# arabaKonsolSematik.net
KiCad netlist of a schematic drawn in Altium Designer
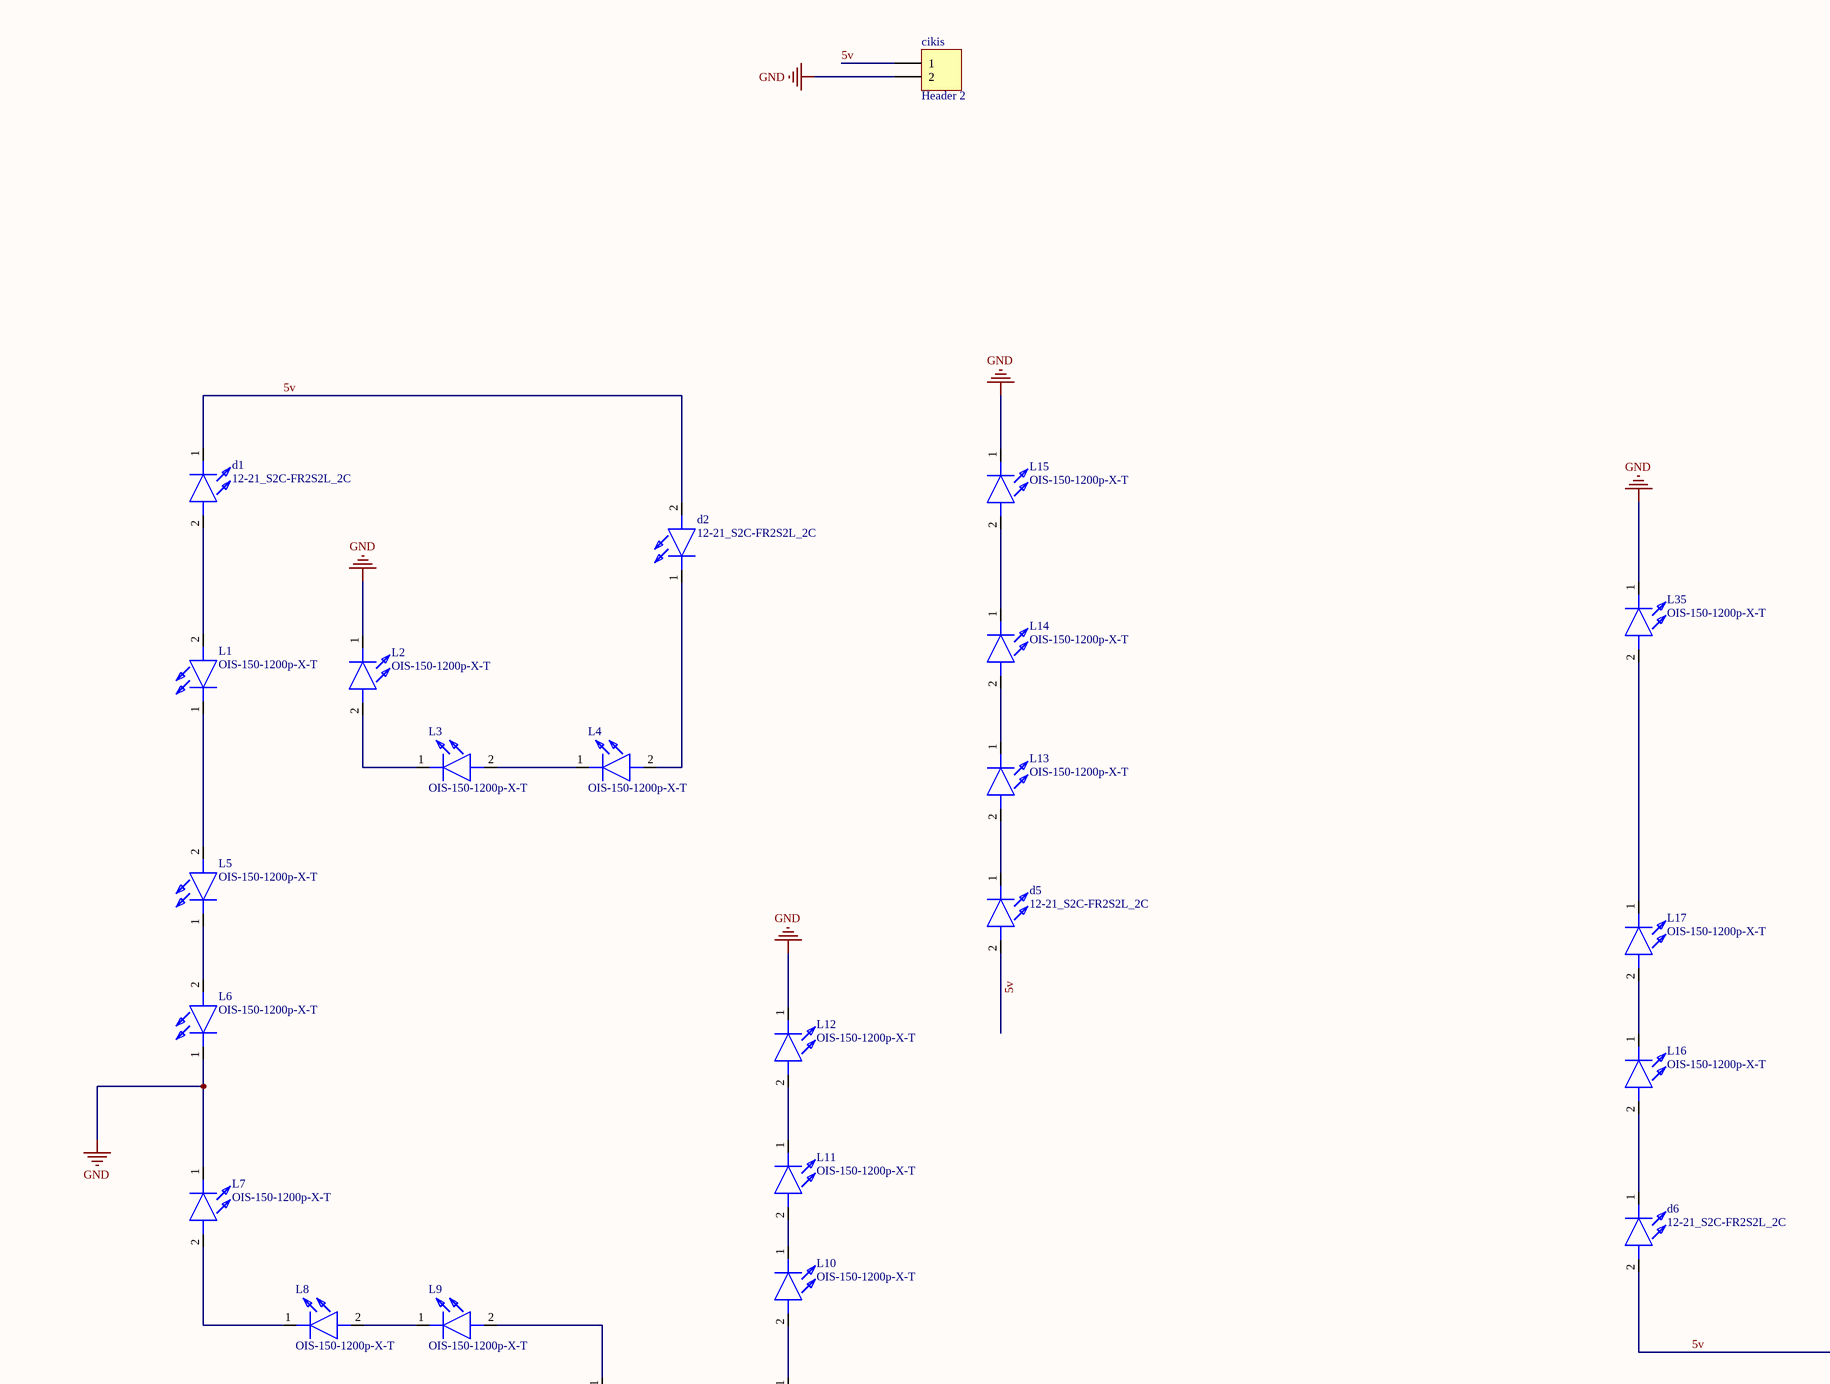
[diagram p0: arabaKonsolSematik.SchDoc, top left]
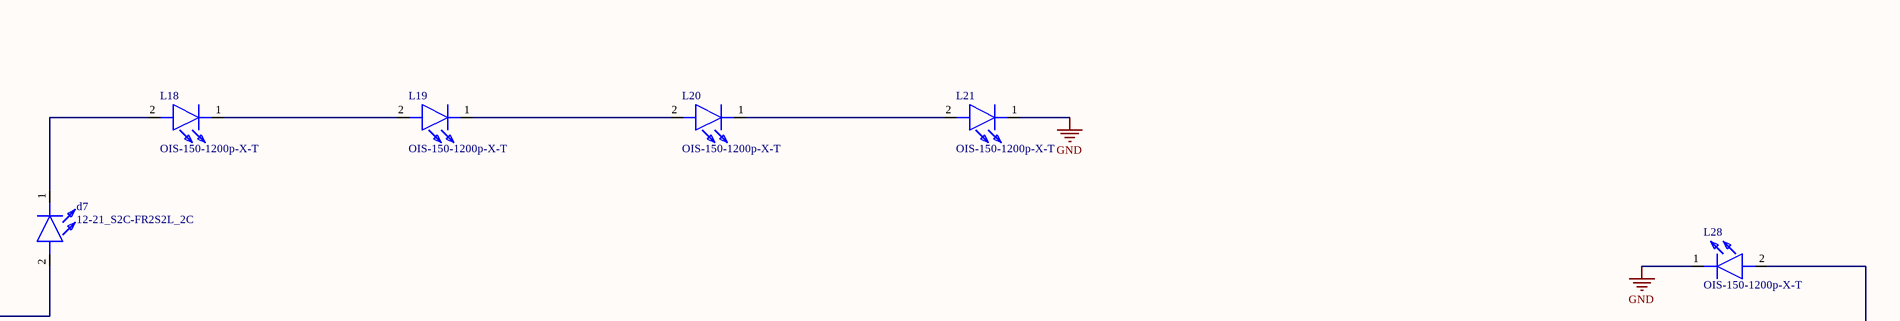
[diagram p1: arabaKonsolSematik.SchDoc, top right]
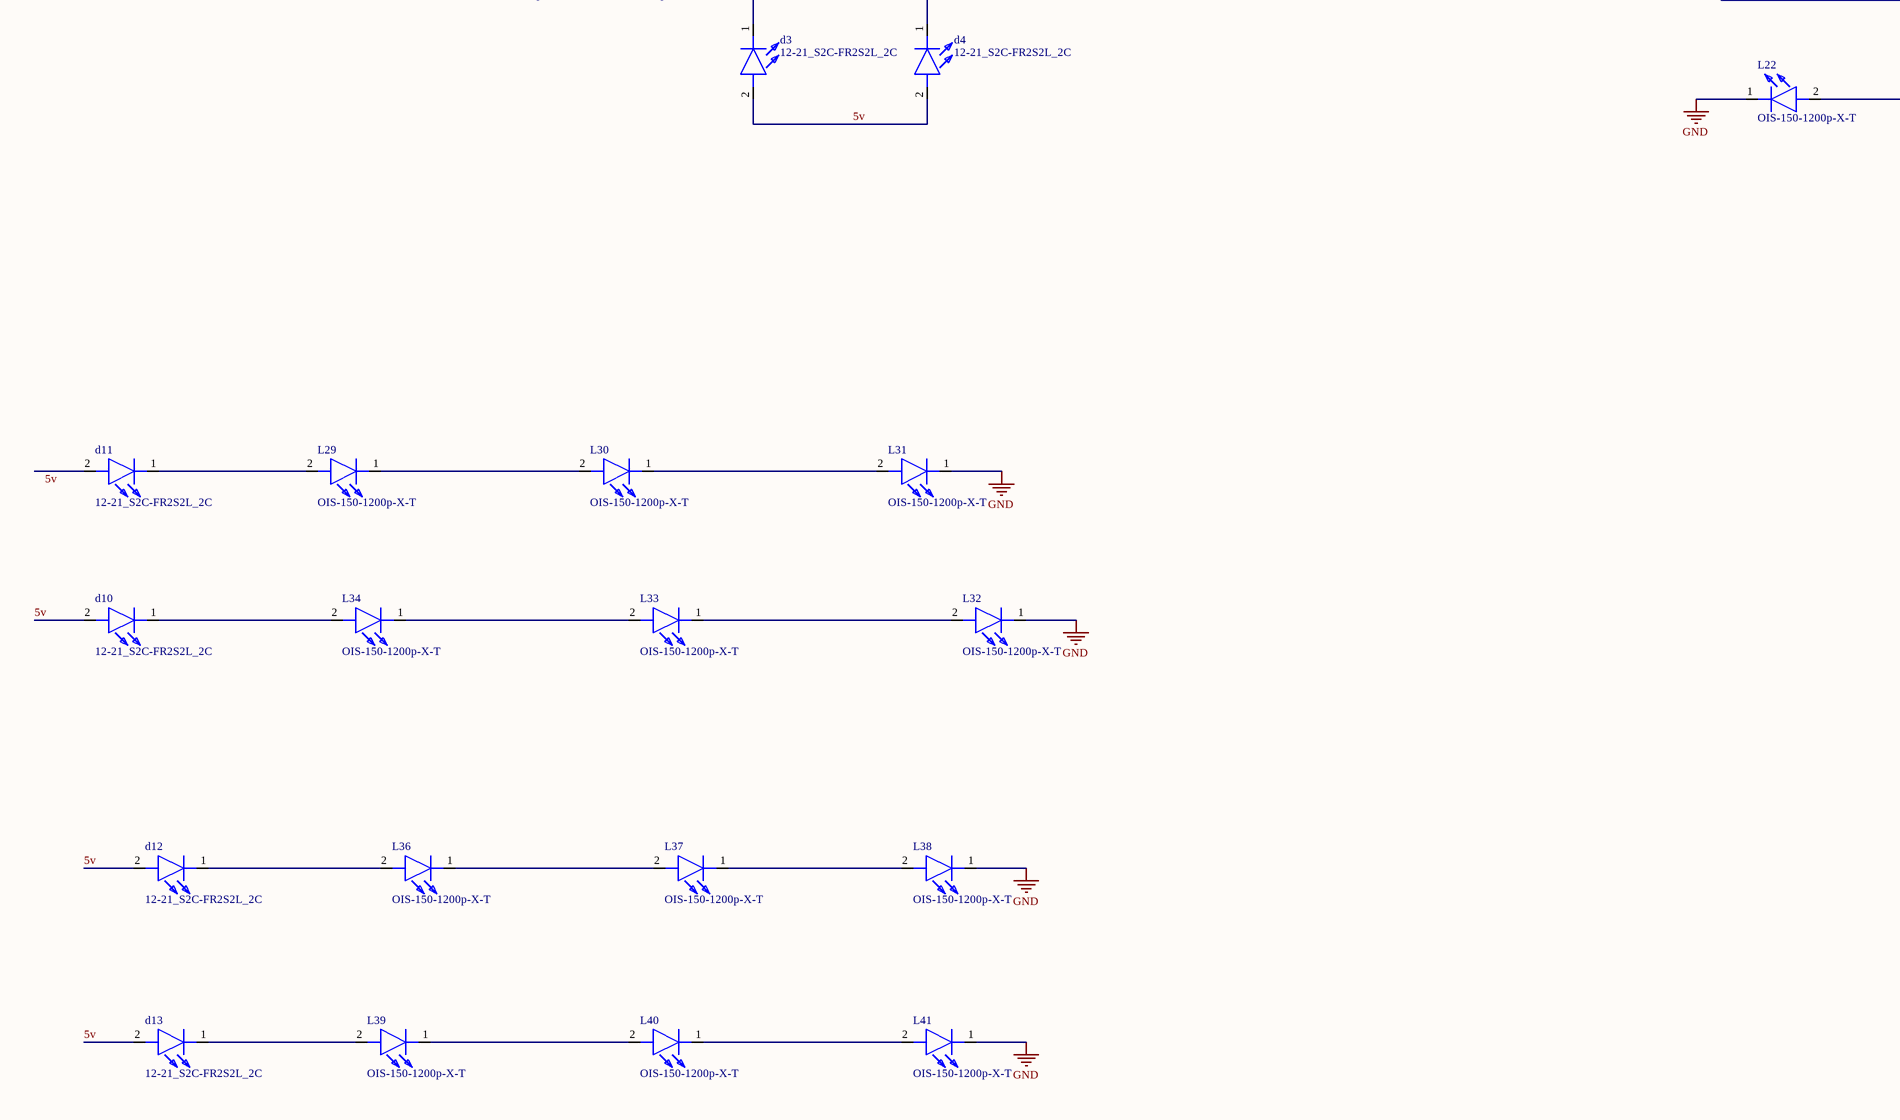
[diagram p2: arabaKonsolSematik.SchDoc, bottom left]
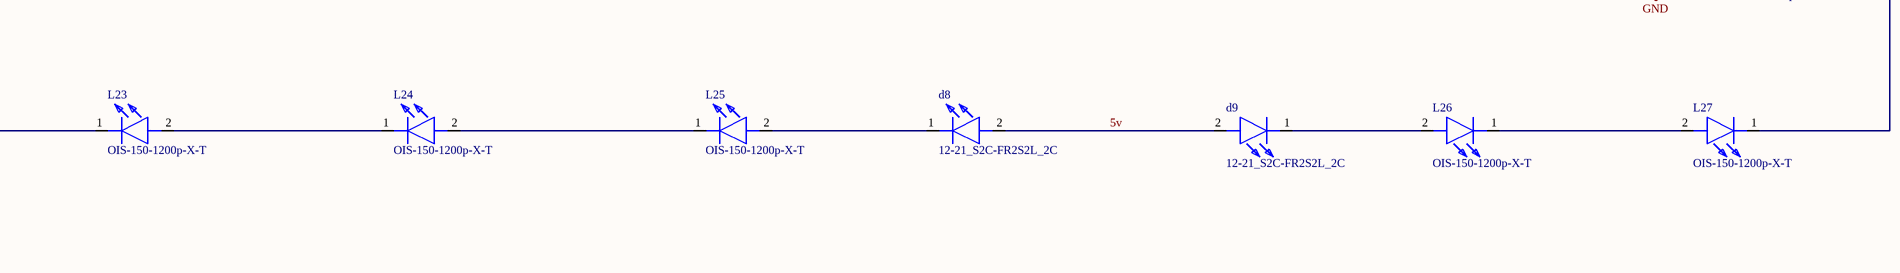
[diagram p3: arabaKonsolSematik.SchDoc, bottom right]

(export (version "E")
  (design (tool "Eeschema 10.0.6"))
  (components
    (comp (ref "cikis")
      (value "Header 2")
      (footprint "HDR1X2")
      (description "Header, 2-Pin")
      (fields (field (name "PUBLISHER") "Altium Limited"))
      (libsource (lib "Miscellaneous Connectors") (part "Header 2"))
    )
    (comp (ref "d1")
      (value "12-21_S2C-FR2S2L_2C")
      (footprint "SamacSys:1221S2CFR2S2L2C")
      (description "LED")
      (fields (field (name "MANUFACTURER_PART_NUMBER") "12-21/S2C-FR2S2L/2C"))
      (libsource (lib "SamacSys") (part "12-21_S2C-FR2S2L_2C"))
    )
    (comp (ref "d2")
      (value "12-21_S2C-FR2S2L_2C")
      (footprint "SamacSys:1221S2CFR2S2L2C")
      (description "LED")
      (fields (field (name "MANUFACTURER_PART_NUMBER") "12-21/S2C-FR2S2L/2C"))
      (libsource (lib "SamacSys") (part "12-21_S2C-FR2S2L_2C"))
    )
    (comp (ref "d3")
      (value "12-21_S2C-FR2S2L_2C")
      (footprint "SamacSys:1221S2CFR2S2L2C")
      (description "LED")
      (fields (field (name "MANUFACTURER_PART_NUMBER") "12-21/S2C-FR2S2L/2C"))
      (libsource (lib "SamacSys") (part "12-21_S2C-FR2S2L_2C"))
    )
    (comp (ref "d4")
      (value "12-21_S2C-FR2S2L_2C")
      (footprint "SamacSys:1221S2CFR2S2L2C")
      (description "LED")
      (fields (field (name "MANUFACTURER_PART_NUMBER") "12-21/S2C-FR2S2L/2C"))
      (libsource (lib "SamacSys") (part "12-21_S2C-FR2S2L_2C"))
    )
    (comp (ref "d5")
      (value "12-21_S2C-FR2S2L_2C")
      (footprint "SamacSys:1221S2CFR2S2L2C")
      (description "LED")
      (fields (field (name "MANUFACTURER_PART_NUMBER") "12-21/S2C-FR2S2L/2C"))
      (libsource (lib "SamacSys") (part "12-21_S2C-FR2S2L_2C"))
    )
    (comp (ref "d6")
      (value "12-21_S2C-FR2S2L_2C")
      (footprint "SamacSys:1221S2CFR2S2L2C")
      (description "LED")
      (fields (field (name "MANUFACTURER_PART_NUMBER") "12-21/S2C-FR2S2L/2C"))
      (libsource (lib "SamacSys") (part "12-21_S2C-FR2S2L_2C"))
    )
    (comp (ref "d7")
      (value "12-21_S2C-FR2S2L_2C")
      (footprint "SamacSys:1221S2CFR2S2L2C")
      (description "LED")
      (fields (field (name "MANUFACTURER_PART_NUMBER") "12-21/S2C-FR2S2L/2C"))
      (libsource (lib "SamacSys") (part "12-21_S2C-FR2S2L_2C"))
    )
    (comp (ref "d8")
      (value "12-21_S2C-FR2S2L_2C")
      (footprint "SamacSys:1221S2CFR2S2L2C")
      (description "LED")
      (fields (field (name "MANUFACTURER_PART_NUMBER") "12-21/S2C-FR2S2L/2C"))
      (libsource (lib "SamacSys") (part "12-21_S2C-FR2S2L_2C"))
    )
    (comp (ref "d9")
      (value "12-21_S2C-FR2S2L_2C")
      (footprint "SamacSys:1221S2CFR2S2L2C")
      (description "LED")
      (fields (field (name "MANUFACTURER_PART_NUMBER") "12-21/S2C-FR2S2L/2C"))
      (libsource (lib "SamacSys") (part "12-21_S2C-FR2S2L_2C"))
    )
    (comp (ref "d10")
      (value "12-21_S2C-FR2S2L_2C")
      (footprint "SamacSys:1221S2CFR2S2L2C")
      (description "LED")
      (fields (field (name "MANUFACTURER_PART_NUMBER") "12-21/S2C-FR2S2L/2C"))
      (libsource (lib "SamacSys") (part "12-21_S2C-FR2S2L_2C"))
    )
    (comp (ref "d11")
      (value "12-21_S2C-FR2S2L_2C")
      (footprint "SamacSys:1221S2CFR2S2L2C")
      (description "LED")
      (fields (field (name "MANUFACTURER_PART_NUMBER") "12-21/S2C-FR2S2L/2C"))
      (libsource (lib "SamacSys") (part "12-21_S2C-FR2S2L_2C"))
    )
    (comp (ref "d12")
      (value "12-21_S2C-FR2S2L_2C")
      (footprint "SamacSys:1221S2CFR2S2L2C")
      (description "LED")
      (fields (field (name "MANUFACTURER_PART_NUMBER") "12-21/S2C-FR2S2L/2C"))
      (libsource (lib "SamacSys") (part "12-21_S2C-FR2S2L_2C"))
    )
    (comp (ref "d13")
      (value "12-21_S2C-FR2S2L_2C")
      (footprint "SamacSys:1221S2CFR2S2L2C")
      (description "LED")
      (fields (field (name "MANUFACTURER_PART_NUMBER") "12-21/S2C-FR2S2L/2C"))
      (libsource (lib "SamacSys") (part "12-21_S2C-FR2S2L_2C"))
    )
    (comp (ref "L1")
      (value "OIS-150-1200p-X-T")
      (footprint "SamacSys:LEDC3216X120N")
      (description "LED")
      (libsource (lib "*") (part "OIS-150-1200p-X-T"))
    )
    (comp (ref "L2")
      (value "OIS-150-1200p-X-T")
      (footprint "SamacSys:LEDC3216X120N")
      (description "LED")
      (libsource (lib "*") (part "OIS-150-1200p-X-T"))
    )
    (comp (ref "L3")
      (value "OIS-150-1200p-X-T")
      (footprint "SamacSys:LEDC3216X120N")
      (description "LED")
      (libsource (lib "*") (part "OIS-150-1200p-X-T"))
    )
    (comp (ref "L4")
      (value "OIS-150-1200p-X-T")
      (footprint "SamacSys:LEDC3216X120N")
      (description "LED")
      (libsource (lib "*") (part "OIS-150-1200p-X-T"))
    )
    (comp (ref "L5")
      (value "OIS-150-1200p-X-T")
      (footprint "SamacSys:LEDC3216X120N")
      (description "LED")
      (libsource (lib "*") (part "OIS-150-1200p-X-T"))
    )
    (comp (ref "L6")
      (value "OIS-150-1200p-X-T")
      (footprint "SamacSys:LEDC3216X120N")
      (description "LED")
      (libsource (lib "*") (part "OIS-150-1200p-X-T"))
    )
    (comp (ref "L7")
      (value "OIS-150-1200p-X-T")
      (footprint "SamacSys:LEDC3216X120N")
      (description "LED")
      (libsource (lib "*") (part "OIS-150-1200p-X-T"))
    )
    (comp (ref "L8")
      (value "OIS-150-1200p-X-T")
      (footprint "SamacSys:LEDC3216X120N")
      (description "LED")
      (libsource (lib "*") (part "OIS-150-1200p-X-T"))
    )
    (comp (ref "L9")
      (value "OIS-150-1200p-X-T")
      (footprint "SamacSys:LEDC3216X120N")
      (description "LED")
      (libsource (lib "*") (part "OIS-150-1200p-X-T"))
    )
    (comp (ref "L10")
      (value "OIS-150-1200p-X-T")
      (footprint "SamacSys:LEDC3216X120N")
      (description "LED")
      (libsource (lib "*") (part "OIS-150-1200p-X-T"))
    )
    (comp (ref "L11")
      (value "OIS-150-1200p-X-T")
      (footprint "SamacSys:LEDC3216X120N")
      (description "LED")
      (libsource (lib "*") (part "OIS-150-1200p-X-T"))
    )
    (comp (ref "L12")
      (value "OIS-150-1200p-X-T")
      (footprint "SamacSys:LEDC3216X120N")
      (description "LED")
      (libsource (lib "*") (part "OIS-150-1200p-X-T"))
    )
    (comp (ref "L13")
      (value "OIS-150-1200p-X-T")
      (footprint "SamacSys:LEDC3216X120N")
      (description "LED")
      (libsource (lib "*") (part "OIS-150-1200p-X-T"))
    )
    (comp (ref "L14")
      (value "OIS-150-1200p-X-T")
      (footprint "SamacSys:LEDC3216X120N")
      (description "LED")
      (libsource (lib "*") (part "OIS-150-1200p-X-T"))
    )
    (comp (ref "L15")
      (value "OIS-150-1200p-X-T")
      (footprint "SamacSys:LEDC3216X120N")
      (description "LED")
      (libsource (lib "*") (part "OIS-150-1200p-X-T"))
    )
    (comp (ref "L16")
      (value "OIS-150-1200p-X-T")
      (footprint "SamacSys:LEDC3216X120N")
      (description "LED")
      (libsource (lib "*") (part "OIS-150-1200p-X-T"))
    )
    (comp (ref "L17")
      (value "OIS-150-1200p-X-T")
      (footprint "SamacSys:LEDC3216X120N")
      (description "LED")
      (libsource (lib "*") (part "OIS-150-1200p-X-T"))
    )
    (comp (ref "L18")
      (value "OIS-150-1200p-X-T")
      (footprint "SamacSys:LEDC3216X120N")
      (description "LED")
      (libsource (lib "*") (part "OIS-150-1200p-X-T"))
    )
    (comp (ref "L19")
      (value "OIS-150-1200p-X-T")
      (footprint "SamacSys:LEDC3216X120N")
      (description "LED")
      (libsource (lib "*") (part "OIS-150-1200p-X-T"))
    )
    (comp (ref "L20")
      (value "OIS-150-1200p-X-T")
      (footprint "SamacSys:LEDC3216X120N")
      (description "LED")
      (libsource (lib "*") (part "OIS-150-1200p-X-T"))
    )
    (comp (ref "L21")
      (value "OIS-150-1200p-X-T")
      (footprint "SamacSys:LEDC3216X120N")
      (description "LED")
      (libsource (lib "*") (part "OIS-150-1200p-X-T"))
    )
    (comp (ref "L22")
      (value "OIS-150-1200p-X-T")
      (footprint "SamacSys:LEDC3216X120N")
      (description "LED")
      (libsource (lib "*") (part "OIS-150-1200p-X-T"))
    )
    (comp (ref "L23")
      (value "OIS-150-1200p-X-T")
      (footprint "SamacSys:LEDC3216X120N")
      (description "LED")
      (libsource (lib "*") (part "OIS-150-1200p-X-T"))
    )
    (comp (ref "L24")
      (value "OIS-150-1200p-X-T")
      (footprint "SamacSys:LEDC3216X120N")
      (description "LED")
      (libsource (lib "*") (part "OIS-150-1200p-X-T"))
    )
    (comp (ref "L25")
      (value "OIS-150-1200p-X-T")
      (footprint "SamacSys:LEDC3216X120N")
      (description "LED")
      (libsource (lib "*") (part "OIS-150-1200p-X-T"))
    )
    (comp (ref "L26")
      (value "OIS-150-1200p-X-T")
      (footprint "SamacSys:LEDC3216X120N")
      (description "LED")
      (libsource (lib "*") (part "OIS-150-1200p-X-T"))
    )
    (comp (ref "L27")
      (value "OIS-150-1200p-X-T")
      (footprint "SamacSys:LEDC3216X120N")
      (description "LED")
      (libsource (lib "*") (part "OIS-150-1200p-X-T"))
    )
    (comp (ref "L28")
      (value "OIS-150-1200p-X-T")
      (footprint "SamacSys:LEDC3216X120N")
      (description "LED")
      (libsource (lib "*") (part "OIS-150-1200p-X-T"))
    )
    (comp (ref "L29")
      (value "OIS-150-1200p-X-T")
      (footprint "SamacSys:LEDC3216X120N")
      (description "LED")
      (libsource (lib "*") (part "OIS-150-1200p-X-T"))
    )
    (comp (ref "L30")
      (value "OIS-150-1200p-X-T")
      (footprint "SamacSys:LEDC3216X120N")
      (description "LED")
      (libsource (lib "*") (part "OIS-150-1200p-X-T"))
    )
    (comp (ref "L31")
      (value "OIS-150-1200p-X-T")
      (footprint "SamacSys:LEDC3216X120N")
      (description "LED")
      (libsource (lib "*") (part "OIS-150-1200p-X-T"))
    )
    (comp (ref "L32")
      (value "OIS-150-1200p-X-T")
      (footprint "SamacSys:LEDC3216X120N")
      (description "LED")
      (libsource (lib "*") (part "OIS-150-1200p-X-T"))
    )
    (comp (ref "L33")
      (value "OIS-150-1200p-X-T")
      (footprint "SamacSys:LEDC3216X120N")
      (description "LED")
      (libsource (lib "*") (part "OIS-150-1200p-X-T"))
    )
    (comp (ref "L34")
      (value "OIS-150-1200p-X-T")
      (footprint "SamacSys:LEDC3216X120N")
      (description "LED")
      (libsource (lib "*") (part "OIS-150-1200p-X-T"))
    )
    (comp (ref "L35")
      (value "OIS-150-1200p-X-T")
      (footprint "SamacSys:LEDC3216X120N")
      (description "LED")
      (libsource (lib "*") (part "OIS-150-1200p-X-T"))
    )
    (comp (ref "L36")
      (value "OIS-150-1200p-X-T")
      (footprint "SamacSys:LEDC3216X120N")
      (description "LED")
      (libsource (lib "*") (part "OIS-150-1200p-X-T"))
    )
    (comp (ref "L37")
      (value "OIS-150-1200p-X-T")
      (footprint "SamacSys:LEDC3216X120N")
      (description "LED")
      (libsource (lib "*") (part "OIS-150-1200p-X-T"))
    )
    (comp (ref "L38")
      (value "OIS-150-1200p-X-T")
      (footprint "SamacSys:LEDC3216X120N")
      (description "LED")
      (libsource (lib "*") (part "OIS-150-1200p-X-T"))
    )
    (comp (ref "L39")
      (value "OIS-150-1200p-X-T")
      (footprint "SamacSys:LEDC3216X120N")
      (description "LED")
      (libsource (lib "*") (part "OIS-150-1200p-X-T"))
    )
    (comp (ref "L40")
      (value "OIS-150-1200p-X-T")
      (footprint "SamacSys:LEDC3216X120N")
      (description "LED")
      (libsource (lib "*") (part "OIS-150-1200p-X-T"))
    )
    (comp (ref "L41")
      (value "OIS-150-1200p-X-T")
      (footprint "SamacSys:LEDC3216X120N")
      (description "LED")
      (libsource (lib "*") (part "OIS-150-1200p-X-T"))
    )
  )
  (nets
    (net (code "1") (name "/5v") (class "Default")
      (node (ref "cikis") (pin "1") (pinfunction "1_1") (pintype "passive"))
      (node (ref "d1") (pin "1") (pinfunction "K_1") (pintype "passive"))
      (node (ref "d10") (pin "2") (pinfunction "A_2") (pintype "passive"))
      (node (ref "d11") (pin "2") (pinfunction "A_2") (pintype "passive"))
      (node (ref "d12") (pin "2") (pinfunction "A_2") (pintype "passive"))
      (node (ref "d13") (pin "2") (pinfunction "A_2") (pintype "passive"))
      (node (ref "d2") (pin "2") (pinfunction "A_2") (pintype "passive"))
      (node (ref "d3") (pin "2") (pinfunction "A_2") (pintype "passive"))
      (node (ref "d4") (pin "2") (pinfunction "A_2") (pintype "passive"))
      (node (ref "d5") (pin "2") (pinfunction "A_2") (pintype "passive"))
      (node (ref "d6") (pin "2") (pinfunction "A_2") (pintype "passive"))
      (node (ref "d7") (pin "2") (pinfunction "A_2") (pintype "passive"))
      (node (ref "d8") (pin "2") (pinfunction "A_2") (pintype "passive"))
      (node (ref "d9") (pin "2") (pinfunction "A_2") (pintype "passive"))
    )
    (net (code "2") (name "GND") (class "Default")
      (node (ref "L12") (pin "1") (pinfunction "K_1") (pintype "passive"))
      (node (ref "L15") (pin "1") (pinfunction "K_1") (pintype "passive"))
      (node (ref "L2") (pin "1") (pinfunction "K_1") (pintype "passive"))
      (node (ref "L21") (pin "1") (pinfunction "K_1") (pintype "passive"))
      (node (ref "L22") (pin "1") (pinfunction "K_1") (pintype "passive"))
      (node (ref "L28") (pin "1") (pinfunction "K_1") (pintype "passive"))
      (node (ref "L31") (pin "1") (pinfunction "K_1") (pintype "passive"))
      (node (ref "L32") (pin "1") (pinfunction "K_1") (pintype "passive"))
      (node (ref "L35") (pin "1") (pinfunction "K_1") (pintype "passive"))
      (node (ref "L38") (pin "1") (pinfunction "K_1") (pintype "passive"))
      (node (ref "L41") (pin "1") (pinfunction "K_1") (pintype "passive"))
      (node (ref "L6") (pin "1") (pinfunction "K_1") (pintype "passive"))
      (node (ref "L7") (pin "1") (pinfunction "K_1") (pintype "passive"))
      (node (ref "cikis") (pin "2") (pinfunction "2_2") (pintype "passive"))
    )
    (net (code "3") (name "Net-(L1-A)") (class "Default")
      (node (ref "L1") (pin "2") (pinfunction "A_2") (pintype "passive"))
      (node (ref "d1") (pin "2") (pinfunction "A_2") (pintype "passive"))
    )
    (net (code "4") (name "Net-(L1-K)") (class "Default")
      (node (ref "L1") (pin "1") (pinfunction "K_1") (pintype "passive"))
      (node (ref "L5") (pin "2") (pinfunction "A_2") (pintype "passive"))
    )
    (net (code "5") (name "Net-(L2-A)") (class "Default")
      (node (ref "L2") (pin "2") (pinfunction "A_2") (pintype "passive"))
      (node (ref "L3") (pin "1") (pinfunction "K_1") (pintype "passive"))
    )
    (net (code "6") (name "Net-(L3-A)") (class "Default")
      (node (ref "L3") (pin "2") (pinfunction "A_2") (pintype "passive"))
      (node (ref "L4") (pin "1") (pinfunction "K_1") (pintype "passive"))
    )
    (net (code "7") (name "Net-(L4-A)") (class "Default")
      (node (ref "L4") (pin "2") (pinfunction "A_2") (pintype "passive"))
      (node (ref "d2") (pin "1") (pinfunction "K_1") (pintype "passive"))
    )
    (net (code "8") (name "Net-(L5-K)") (class "Default")
      (node (ref "L5") (pin "1") (pinfunction "K_1") (pintype "passive"))
      (node (ref "L6") (pin "2") (pinfunction "A_2") (pintype "passive"))
    )
    (net (code "9") (name "Net-(L7-A)") (class "Default")
      (node (ref "L7") (pin "2") (pinfunction "A_2") (pintype "passive"))
      (node (ref "L8") (pin "1") (pinfunction "K_1") (pintype "passive"))
    )
    (net (code "10") (name "Net-(L8-A)") (class "Default")
      (node (ref "L8") (pin "2") (pinfunction "A_2") (pintype "passive"))
      (node (ref "L9") (pin "1") (pinfunction "K_1") (pintype "passive"))
    )
    (net (code "11") (name "Net-(L9-A)") (class "Default")
      (node (ref "L9") (pin "2") (pinfunction "A_2") (pintype "passive"))
      (node (ref "d3") (pin "1") (pinfunction "K_1") (pintype "passive"))
    )
    (net (code "12") (name "Net-(L10-A)") (class "Default")
      (node (ref "L10") (pin "2") (pinfunction "A_2") (pintype "passive"))
      (node (ref "d4") (pin "1") (pinfunction "K_1") (pintype "passive"))
    )
    (net (code "13") (name "Net-(L10-K)") (class "Default")
      (node (ref "L10") (pin "1") (pinfunction "K_1") (pintype "passive"))
      (node (ref "L11") (pin "2") (pinfunction "A_2") (pintype "passive"))
    )
    (net (code "14") (name "Net-(L11-K)") (class "Default")
      (node (ref "L11") (pin "1") (pinfunction "K_1") (pintype "passive"))
      (node (ref "L12") (pin "2") (pinfunction "A_2") (pintype "passive"))
    )
    (net (code "15") (name "Net-(L13-A)") (class "Default")
      (node (ref "L13") (pin "2") (pinfunction "A_2") (pintype "passive"))
      (node (ref "d5") (pin "1") (pinfunction "K_1") (pintype "passive"))
    )
    (net (code "16") (name "Net-(L13-K)") (class "Default")
      (node (ref "L13") (pin "1") (pinfunction "K_1") (pintype "passive"))
      (node (ref "L14") (pin "2") (pinfunction "A_2") (pintype "passive"))
    )
    (net (code "17") (name "Net-(L14-K)") (class "Default")
      (node (ref "L14") (pin "1") (pinfunction "K_1") (pintype "passive"))
      (node (ref "L15") (pin "2") (pinfunction "A_2") (pintype "passive"))
    )
    (net (code "18") (name "Net-(L16-A)") (class "Default")
      (node (ref "L16") (pin "2") (pinfunction "A_2") (pintype "passive"))
      (node (ref "d6") (pin "1") (pinfunction "K_1") (pintype "passive"))
    )
    (net (code "19") (name "Net-(L16-K)") (class "Default")
      (node (ref "L16") (pin "1") (pinfunction "K_1") (pintype "passive"))
      (node (ref "L17") (pin "2") (pinfunction "A_2") (pintype "passive"))
    )
    (net (code "20") (name "Net-(L17-K)") (class "Default")
      (node (ref "L17") (pin "1") (pinfunction "K_1") (pintype "passive"))
      (node (ref "L35") (pin "2") (pinfunction "A_2") (pintype "passive"))
    )
    (net (code "21") (name "Net-(L18-A)") (class "Default")
      (node (ref "L18") (pin "2") (pinfunction "A_2") (pintype "passive"))
      (node (ref "d7") (pin "1") (pinfunction "K_1") (pintype "passive"))
    )
    (net (code "22") (name "Net-(L18-K)") (class "Default")
      (node (ref "L18") (pin "1") (pinfunction "K_1") (pintype "passive"))
      (node (ref "L19") (pin "2") (pinfunction "A_2") (pintype "passive"))
    )
    (net (code "23") (name "Net-(L19-K)") (class "Default")
      (node (ref "L19") (pin "1") (pinfunction "K_1") (pintype "passive"))
      (node (ref "L20") (pin "2") (pinfunction "A_2") (pintype "passive"))
    )
    (net (code "24") (name "Net-(L20-K)") (class "Default")
      (node (ref "L20") (pin "1") (pinfunction "K_1") (pintype "passive"))
      (node (ref "L21") (pin "2") (pinfunction "A_2") (pintype "passive"))
    )
    (net (code "25") (name "Net-(L22-A)") (class "Default")
      (node (ref "L22") (pin "2") (pinfunction "A_2") (pintype "passive"))
      (node (ref "L23") (pin "1") (pinfunction "K_1") (pintype "passive"))
    )
    (net (code "26") (name "Net-(L23-A)") (class "Default")
      (node (ref "L23") (pin "2") (pinfunction "A_2") (pintype "passive"))
      (node (ref "L24") (pin "1") (pinfunction "K_1") (pintype "passive"))
    )
    (net (code "27") (name "Net-(L24-A)") (class "Default")
      (node (ref "L24") (pin "2") (pinfunction "A_2") (pintype "passive"))
      (node (ref "L25") (pin "1") (pinfunction "K_1") (pintype "passive"))
    )
    (net (code "28") (name "Net-(L25-A)") (class "Default")
      (node (ref "L25") (pin "2") (pinfunction "A_2") (pintype "passive"))
      (node (ref "d8") (pin "1") (pinfunction "K_1") (pintype "passive"))
    )
    (net (code "29") (name "Net-(L26-A)") (class "Default")
      (node (ref "L26") (pin "2") (pinfunction "A_2") (pintype "passive"))
      (node (ref "d9") (pin "1") (pinfunction "K_1") (pintype "passive"))
    )
    (net (code "30") (name "Net-(L26-K)") (class "Default")
      (node (ref "L26") (pin "1") (pinfunction "K_1") (pintype "passive"))
      (node (ref "L27") (pin "2") (pinfunction "A_2") (pintype "passive"))
    )
    (net (code "31") (name "Net-(L27-K)") (class "Default")
      (node (ref "L27") (pin "1") (pinfunction "K_1") (pintype "passive"))
      (node (ref "L28") (pin "2") (pinfunction "A_2") (pintype "passive"))
    )
    (net (code "32") (name "Net-(L29-A)") (class "Default")
      (node (ref "L29") (pin "2") (pinfunction "A_2") (pintype "passive"))
      (node (ref "d11") (pin "1") (pinfunction "K_1") (pintype "passive"))
    )
    (net (code "33") (name "Net-(L29-K)") (class "Default")
      (node (ref "L29") (pin "1") (pinfunction "K_1") (pintype "passive"))
      (node (ref "L30") (pin "2") (pinfunction "A_2") (pintype "passive"))
    )
    (net (code "34") (name "Net-(L30-K)") (class "Default")
      (node (ref "L30") (pin "1") (pinfunction "K_1") (pintype "passive"))
      (node (ref "L31") (pin "2") (pinfunction "A_2") (pintype "passive"))
    )
    (net (code "35") (name "Net-(L32-A)") (class "Default")
      (node (ref "L32") (pin "2") (pinfunction "A_2") (pintype "passive"))
      (node (ref "L33") (pin "1") (pinfunction "K_1") (pintype "passive"))
    )
    (net (code "36") (name "Net-(L33-A)") (class "Default")
      (node (ref "L33") (pin "2") (pinfunction "A_2") (pintype "passive"))
      (node (ref "L34") (pin "1") (pinfunction "K_1") (pintype "passive"))
    )
    (net (code "37") (name "Net-(L34-A)") (class "Default")
      (node (ref "L34") (pin "2") (pinfunction "A_2") (pintype "passive"))
      (node (ref "d10") (pin "1") (pinfunction "K_1") (pintype "passive"))
    )
    (net (code "38") (name "Net-(L36-A)") (class "Default")
      (node (ref "L36") (pin "2") (pinfunction "A_2") (pintype "passive"))
      (node (ref "d12") (pin "1") (pinfunction "K_1") (pintype "passive"))
    )
    (net (code "39") (name "Net-(L36-K)") (class "Default")
      (node (ref "L36") (pin "1") (pinfunction "K_1") (pintype "passive"))
      (node (ref "L37") (pin "2") (pinfunction "A_2") (pintype "passive"))
    )
    (net (code "40") (name "Net-(L37-K)") (class "Default")
      (node (ref "L37") (pin "1") (pinfunction "K_1") (pintype "passive"))
      (node (ref "L38") (pin "2") (pinfunction "A_2") (pintype "passive"))
    )
    (net (code "41") (name "Net-(L39-A)") (class "Default")
      (node (ref "L39") (pin "2") (pinfunction "A_2") (pintype "passive"))
      (node (ref "d13") (pin "1") (pinfunction "K_1") (pintype "passive"))
    )
    (net (code "42") (name "Net-(L39-K)") (class "Default")
      (node (ref "L39") (pin "1") (pinfunction "K_1") (pintype "passive"))
      (node (ref "L40") (pin "2") (pinfunction "A_2") (pintype "passive"))
    )
    (net (code "43") (name "Net-(L40-K)") (class "Default")
      (node (ref "L40") (pin "1") (pinfunction "K_1") (pintype "passive"))
      (node (ref "L41") (pin "2") (pinfunction "A_2") (pintype "passive"))
    )
  )
)
